# BME280_breakout.net
KiCad netlist of a schematic drawn in EAGLE
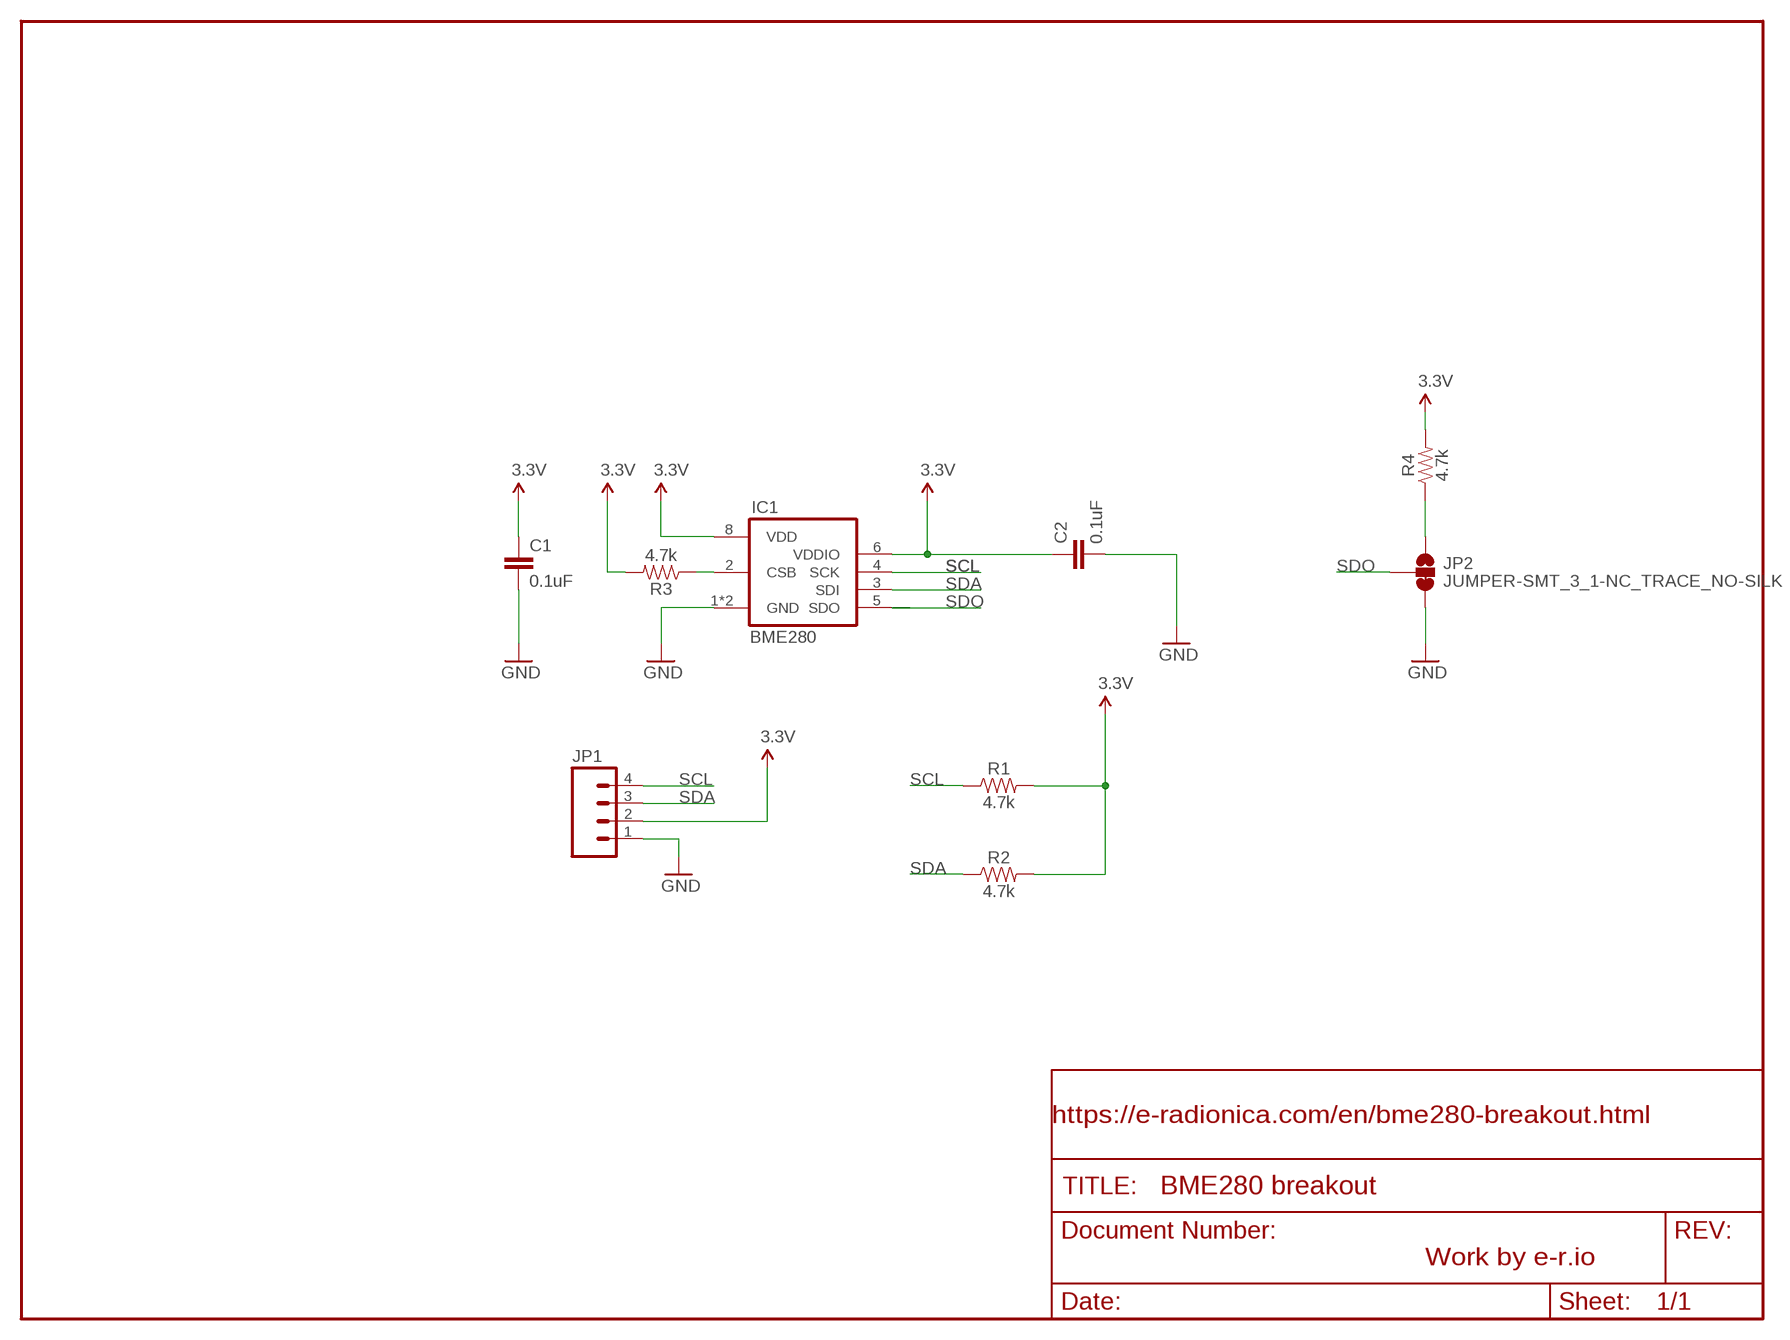
[diagram p0: schematic, sheet 1]

(export (version "E")
  (design (tool "Eeschema 10.0.6"))
  (components
    (comp (ref "C1")
      (value "0.1uF")
      (footprint "eagle-import:0603")
      (libsource (lib "eagle-import") (part "0.1UF-0603-25V-(+80/-20%)"))
    )
    (comp (ref "C2")
      (value "0.1uF")
      (footprint "eagle-import:0603")
      (libsource (lib "eagle-import") (part "0.1UF-0603-25V-(+80/-20%)"))
    )
    (comp (ref "IC1")
      (value "BME280")
      (footprint "eagle-import:BME280")
      (libsource (lib "eagle-import") (part "BME280"))
    )
    (comp (ref "JP1")
      (value "M04PTH")
      (footprint "eagle-import:1X04")
      (libsource (lib "eagle-import") (part "M04PTH"))
    )
    (comp (ref "JP2")
      (value "JUMPER-SMT_3_1-NC_TRACE_NO-SILK")
      (footprint "eagle-import:SMT-JUMPER_3_1-NC_TRACE_NO-SILK")
      (libsource (lib "eagle-import") (part "JUMPER-SMT_3_1-NC_TRACE_NO-SILK"))
    )
    (comp (ref "R1")
      (value "4.7k")
      (footprint "eagle-import:0603")
      (libsource (lib "eagle-import") (part "4.7KOHM-0603-1/10W-1%"))
    )
    (comp (ref "R2")
      (value "4.7k")
      (footprint "eagle-import:0603")
      (libsource (lib "eagle-import") (part "4.7KOHM-0603-1/10W-1%"))
    )
    (comp (ref "R3")
      (value "4.7k")
      (footprint "eagle-import:0603")
      (libsource (lib "eagle-import") (part "4.7KOHM-0603-1/10W-1%"))
    )
    (comp (ref "R4")
      (value "4.7k")
      (footprint "eagle-import:0603")
      (libsource (lib "eagle-import") (part "4.7KOHM-0603-1/10W-1%"))
    )
  )
  (nets
    (net (code "1") (name "/SCL") (class "Default")
      (node (ref "IC1") (pin "4") (pinfunction "SCK_4") (pintype "bidirectional"))
      (node (ref "JP1") (pin "4") (pinfunction "4_4") (pintype "passive"))
      (node (ref "R1") (pin "1") (pinfunction "1_1") (pintype "passive"))
    )
    (net (code "2") (name "/SDA") (class "Default")
      (node (ref "IC1") (pin "3") (pinfunction "SDI_3") (pintype "bidirectional"))
      (node (ref "JP1") (pin "3") (pinfunction "3_3") (pintype "passive"))
      (node (ref "R2") (pin "1") (pinfunction "1_1") (pintype "passive"))
    )
    (net (code "3") (name "/SDO") (class "Default")
      (node (ref "IC1") (pin "5") (pinfunction "SDO_5") (pintype "input"))
      (node (ref "JP2") (pin "2") (pinfunction "2_2") (pintype "passive"))
    )
    (net (code "4") (name "3.3V") (class "Default")
      (node (ref "C1") (pin "1") (pinfunction "1_1") (pintype "passive"))
      (node (ref "C2") (pin "1") (pinfunction "1_1") (pintype "passive"))
      (node (ref "IC1") (pin "6") (pinfunction "VDDIO_6") (pintype "power_in"))
      (node (ref "IC1") (pin "8") (pinfunction "VDD_8") (pintype "power_in"))
      (node (ref "JP1") (pin "2") (pinfunction "2_2") (pintype "passive"))
      (node (ref "R1") (pin "2") (pinfunction "2_2") (pintype "passive"))
      (node (ref "R2") (pin "2") (pinfunction "2_2") (pintype "passive"))
      (node (ref "R3") (pin "2") (pinfunction "2_2") (pintype "passive"))
      (node (ref "R4") (pin "2") (pinfunction "2_2") (pintype "passive"))
    )
    (net (code "5") (name "GND") (class "Default")
      (node (ref "C1") (pin "2") (pinfunction "2_2") (pintype "passive"))
      (node (ref "C2") (pin "2") (pinfunction "2_2") (pintype "passive"))
      (node (ref "IC1") (pin "1") (pinfunction "GND_1") (pintype "power_in"))
      (node (ref "IC1") (pin "7") (pinfunction "GND_7") (pintype "power_in"))
      (node (ref "JP1") (pin "1") (pinfunction "1_1") (pintype "passive"))
      (node (ref "JP2") (pin "3") (pinfunction "3_3") (pintype "passive"))
    )
    (net (code "6") (name "Net-(IC1-CSB)") (class "Default")
      (node (ref "IC1") (pin "2") (pinfunction "CSB_2") (pintype "input"))
      (node (ref "R3") (pin "1") (pinfunction "1_1") (pintype "passive"))
    )
    (net (code "7") (name "Net-(JP2-Pad1)") (class "Default")
      (node (ref "JP2") (pin "1") (pinfunction "1_1") (pintype "passive"))
      (node (ref "R4") (pin "1") (pinfunction "1_1") (pintype "passive"))
    )
  )
)
